# BareDuino_schematic.net
KiCad netlist of a schematic drawn in EAGLE
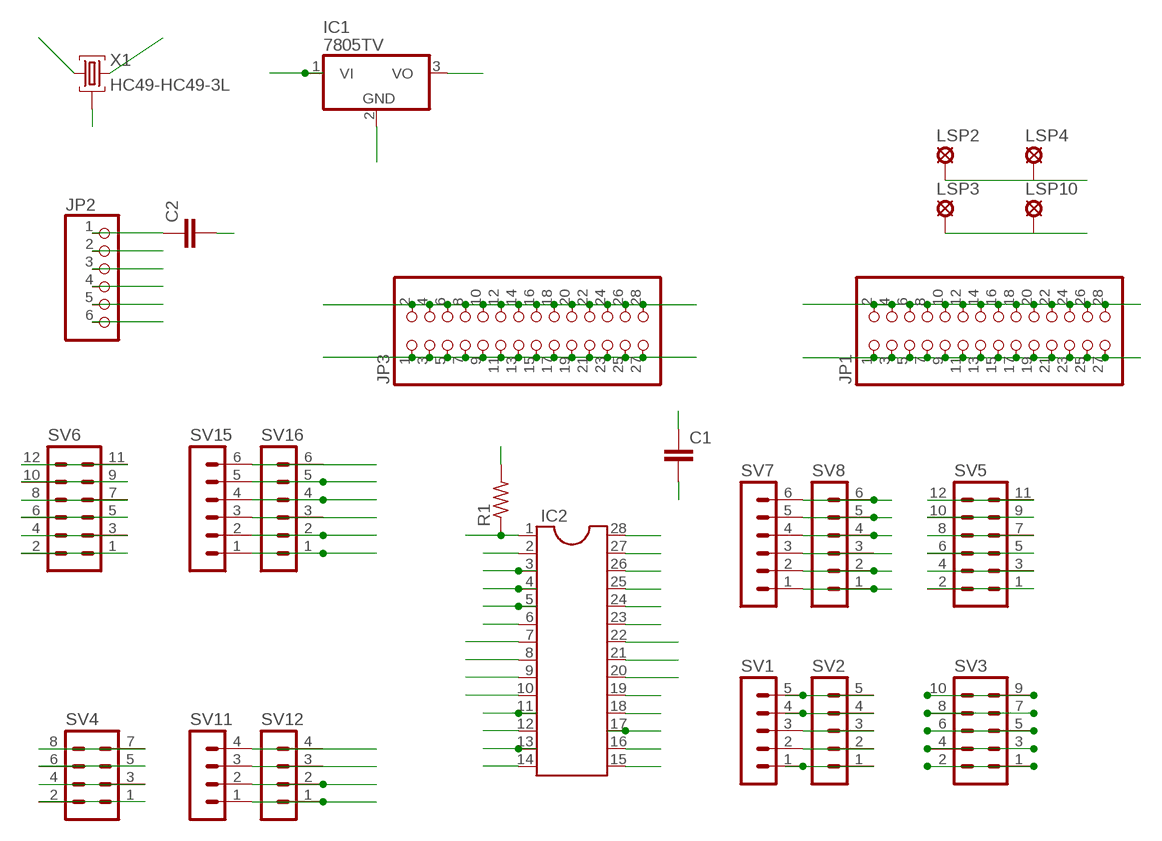
[diagram p0: schematic, sheet 1]

(export (version "E")
  (design (tool "Eeschema 10.0.6"))
  (components
    (comp (ref "C1")
      (value "C5/2.5")
      (footprint "eagle-import:C5B2.5")
      (libsource (lib "eagle-import") (part "C5/2.5"))
    )
    (comp (ref "C2")
      (value "C5/2.5")
      (footprint "eagle-import:C5B2.5")
      (libsource (lib "eagle-import") (part "C5/2.5"))
    )
    (comp (ref "IC1")
      (value "7805TV")
      (footprint "eagle-import:TO220V")
      (libsource (lib "eagle-import") (part "78TV05"))
    )
    (comp (ref "IC2")
      (value "DIL28-3")
      (footprint "eagle-import:DIL28-3")
      (libsource (lib "eagle-import") (part "DIL28-3"))
    )
    (comp (ref "JP1")
      (value "PINHD-2X14")
      (footprint "eagle-import:2X14")
      (libsource (lib "eagle-import") (part "PINHD-2X14"))
    )
    (comp (ref "JP2")
      (value "PINHD-1X6")
      (footprint "eagle-import:1X06")
      (libsource (lib "eagle-import") (part "PINHD-1X6"))
    )
    (comp (ref "JP3")
      (value "PINHD-2X14")
      (footprint "eagle-import:2X14")
      (libsource (lib "eagle-import") (part "PINHD-2X14"))
    )
    (comp (ref "LSP2")
      (value "SE14")
      (footprint "eagle-import:SE14")
      (libsource (lib "eagle-import") (part "SE14"))
    )
    (comp (ref "LSP3")
      (value "SE14")
      (footprint "eagle-import:SE14")
      (libsource (lib "eagle-import") (part "SE14"))
    )
    (comp (ref "LSP4")
      (value "LSP10")
      (footprint "eagle-import:LSP10")
      (libsource (lib "eagle-import") (part "LSP10"))
    )
    (comp (ref "LSP10")
      (value "LSP10")
      (footprint "eagle-import:LSP10")
      (libsource (lib "eagle-import") (part "LSP10"))
    )
    (comp (ref "R1")
      (value "R-US_0204/5")
      (footprint "eagle-import:0204_5")
      (libsource (lib "eagle-import") (part "R-US_0204/5"))
    )
    (comp (ref "SV1")
      (value "MA05-1")
      (footprint "eagle-import:MA05-1")
      (libsource (lib "eagle-import") (part "MA05-1"))
    )
    (comp (ref "SV2")
      (value "MA05-1")
      (footprint "eagle-import:MA05-1")
      (libsource (lib "eagle-import") (part "MA05-1"))
    )
    (comp (ref "SV3")
      (value "MA05-2")
      (footprint "eagle-import:MA05-2")
      (libsource (lib "eagle-import") (part "MA05-2"))
    )
    (comp (ref "SV4")
      (value "MA04-2")
      (footprint "eagle-import:MA04-2")
      (libsource (lib "eagle-import") (part "MA04-2"))
    )
    (comp (ref "SV5")
      (value "MA06-2")
      (footprint "eagle-import:MA06-2")
      (libsource (lib "eagle-import") (part "MA06-2"))
    )
    (comp (ref "SV6")
      (value "MA06-2")
      (footprint "eagle-import:MA06-2")
      (libsource (lib "eagle-import") (part "MA06-2"))
    )
    (comp (ref "SV7")
      (value "MA06-1")
      (footprint "eagle-import:MA06-1")
      (libsource (lib "eagle-import") (part "MA06-1"))
    )
    (comp (ref "SV8")
      (value "MA06-1")
      (footprint "eagle-import:MA06-1")
      (libsource (lib "eagle-import") (part "MA06-1"))
    )
    (comp (ref "SV11")
      (value "MA04-1")
      (footprint "eagle-import:MA04-1")
      (libsource (lib "eagle-import") (part "MA04-1"))
    )
    (comp (ref "SV12")
      (value "MA04-1")
      (footprint "eagle-import:MA04-1")
      (libsource (lib "eagle-import") (part "MA04-1"))
    )
    (comp (ref "SV15")
      (value "MA06-1")
      (footprint "eagle-import:MA06-1")
      (libsource (lib "eagle-import") (part "MA06-1"))
    )
    (comp (ref "SV16")
      (value "MA06-1")
      (footprint "eagle-import:MA06-1")
      (libsource (lib "eagle-import") (part "MA06-1"))
    )
    (comp (ref "X1")
      (value "HC49-HC49-3L")
      (footprint "eagle-import:HC49-3L")
      (libsource (lib "eagle-import") (part "HC49-HC49-3L"))
    )
  )
  (nets
    (net (code "1") (name "/CLK-9") (class "Default")
      (node (ref "IC2") (pin "9") (pinfunction "9_9") (pintype "passive"))
      (node (ref "X1") (pin "1") (pinfunction "1_1") (pintype "passive"))
    )
    (net (code "2") (name "/CLK-10") (class "Default")
      (node (ref "IC2") (pin "10") (pinfunction "10_10") (pintype "passive"))
      (node (ref "X1") (pin "3") (pinfunction "3_3") (pintype "passive"))
    )
    (net (code "3") (name "/DIP2") (class "Default")
      (node (ref "IC2") (pin "2") (pinfunction "2_2") (pintype "passive"))
      (node (ref "JP2") (pin "3") (pinfunction "3_3") (pintype "passive"))
      (node (ref "SV15") (pin "5") (pinfunction "5_5") (pintype "passive"))
      (node (ref "SV16") (pin "5") (pinfunction "5_5") (pintype "passive"))
    )
    (net (code "4") (name "/DIP3") (class "Default")
      (node (ref "IC2") (pin "3") (pinfunction "3_3") (pintype "passive"))
      (node (ref "JP2") (pin "2") (pinfunction "2_2") (pintype "passive"))
      (node (ref "SV15") (pin "4") (pinfunction "4_4") (pintype "passive"))
      (node (ref "SV16") (pin "4") (pinfunction "4_4") (pintype "passive"))
    )
    (net (code "5") (name "/DIP4") (class "Default")
      (node (ref "IC2") (pin "4") (pinfunction "4_4") (pintype "passive"))
      (node (ref "SV15") (pin "3") (pinfunction "3_3") (pintype "passive"))
      (node (ref "SV16") (pin "3") (pinfunction "3_3") (pintype "passive"))
    )
    (net (code "6") (name "/DIP5") (class "Default")
      (node (ref "IC2") (pin "5") (pinfunction "5_5") (pintype "passive"))
      (node (ref "SV15") (pin "2") (pinfunction "2_2") (pintype "passive"))
      (node (ref "SV16") (pin "2") (pinfunction "2_2") (pintype "passive"))
    )
    (net (code "7") (name "/DIP6") (class "Default")
      (node (ref "IC2") (pin "6") (pinfunction "6_6") (pintype "passive"))
      (node (ref "SV15") (pin "1") (pinfunction "1_1") (pintype "passive"))
      (node (ref "SV16") (pin "1") (pinfunction "1_1") (pintype "passive"))
    )
    (net (code "8") (name "/DIP11") (class "Default")
      (node (ref "IC2") (pin "11") (pinfunction "11_11") (pintype "passive"))
      (node (ref "SV11") (pin "4") (pinfunction "4_4") (pintype "passive"))
      (node (ref "SV12") (pin "4") (pinfunction "4_4") (pintype "passive"))
    )
    (net (code "9") (name "/DIP12") (class "Default")
      (node (ref "IC2") (pin "12") (pinfunction "12_12") (pintype "passive"))
      (node (ref "SV11") (pin "3") (pinfunction "3_3") (pintype "passive"))
      (node (ref "SV12") (pin "3") (pinfunction "3_3") (pintype "passive"))
    )
    (net (code "10") (name "/DIP13") (class "Default")
      (node (ref "IC2") (pin "13") (pinfunction "13_13") (pintype "passive"))
      (node (ref "SV11") (pin "2") (pinfunction "2_2") (pintype "passive"))
      (node (ref "SV12") (pin "2") (pinfunction "2_2") (pintype "passive"))
    )
    (net (code "11") (name "/DIP14") (class "Default")
      (node (ref "IC2") (pin "14") (pinfunction "14_14") (pintype "passive"))
      (node (ref "SV11") (pin "1") (pinfunction "1_1") (pintype "passive"))
      (node (ref "SV12") (pin "1") (pinfunction "1_1") (pintype "passive"))
    )
    (net (code "12") (name "/DIP15") (class "Default")
      (node (ref "IC2") (pin "15") (pinfunction "15_15") (pintype "passive"))
      (node (ref "SV1") (pin "1") (pinfunction "1_1") (pintype "passive"))
      (node (ref "SV2") (pin "1") (pinfunction "1_1") (pintype "passive"))
    )
    (net (code "13") (name "/DIP16") (class "Default")
      (node (ref "IC2") (pin "16") (pinfunction "16_16") (pintype "passive"))
      (node (ref "SV1") (pin "2") (pinfunction "2_2") (pintype "passive"))
      (node (ref "SV2") (pin "2") (pinfunction "2_2") (pintype "passive"))
    )
    (net (code "14") (name "/DIP17") (class "Default")
      (node (ref "IC2") (pin "17") (pinfunction "17_17") (pintype "passive"))
      (node (ref "SV1") (pin "3") (pinfunction "3_3") (pintype "passive"))
      (node (ref "SV2") (pin "3") (pinfunction "3_3") (pintype "passive"))
    )
    (net (code "15") (name "/DIP18") (class "Default")
      (node (ref "IC2") (pin "18") (pinfunction "18_18") (pintype "passive"))
      (node (ref "SV1") (pin "4") (pinfunction "4_4") (pintype "passive"))
      (node (ref "SV2") (pin "4") (pinfunction "4_4") (pintype "passive"))
    )
    (net (code "16") (name "/DIP19") (class "Default")
      (node (ref "IC2") (pin "19") (pinfunction "19_19") (pintype "passive"))
      (node (ref "SV1") (pin "5") (pinfunction "5_5") (pintype "passive"))
      (node (ref "SV2") (pin "5") (pinfunction "5_5") (pintype "passive"))
    )
    (net (code "17") (name "/DIP23") (class "Default")
      (node (ref "IC2") (pin "23") (pinfunction "23_23") (pintype "passive"))
      (node (ref "SV7") (pin "1") (pinfunction "1_1") (pintype "passive"))
      (node (ref "SV8") (pin "1") (pinfunction "1_1") (pintype "passive"))
    )
    (net (code "18") (name "/DIP24") (class "Default")
      (node (ref "IC2") (pin "24") (pinfunction "24_24") (pintype "passive"))
      (node (ref "SV7") (pin "2") (pinfunction "2_2") (pintype "passive"))
      (node (ref "SV8") (pin "2") (pinfunction "2_2") (pintype "passive"))
    )
    (net (code "19") (name "/DIP25") (class "Default")
      (node (ref "IC2") (pin "25") (pinfunction "25_25") (pintype "passive"))
      (node (ref "SV7") (pin "3") (pinfunction "3_3") (pintype "passive"))
      (node (ref "SV8") (pin "3") (pinfunction "3_3") (pintype "passive"))
    )
    (net (code "20") (name "/DIP26") (class "Default")
      (node (ref "IC2") (pin "26") (pinfunction "26_26") (pintype "passive"))
      (node (ref "SV7") (pin "4") (pinfunction "4_4") (pintype "passive"))
      (node (ref "SV8") (pin "4") (pinfunction "4_4") (pintype "passive"))
    )
    (net (code "21") (name "/DIP27") (class "Default")
      (node (ref "IC2") (pin "27") (pinfunction "27_27") (pintype "passive"))
      (node (ref "SV7") (pin "5") (pinfunction "5_5") (pintype "passive"))
      (node (ref "SV8") (pin "5") (pinfunction "5_5") (pintype "passive"))
    )
    (net (code "22") (name "/DIP28") (class "Default")
      (node (ref "IC2") (pin "28") (pinfunction "28_28") (pintype "passive"))
      (node (ref "SV7") (pin "6") (pinfunction "6_6") (pintype "passive"))
      (node (ref "SV8") (pin "6") (pinfunction "6_6") (pintype "passive"))
    )
    (net (code "23") (name "/GND") (class "Default")
      (node (ref "C1") (pin "1") (pinfunction "1_1") (pintype "passive"))
      (node (ref "IC1") (pin "2") (pinfunction "GND_2") (pintype "passive"))
      (node (ref "IC2") (pin "22") (pinfunction "22_22") (pintype "passive"))
      (node (ref "IC2") (pin "8") (pinfunction "8_8") (pintype "passive"))
      (node (ref "JP1") (pin "10") (pinfunction "10_10") (pintype "passive"))
      (node (ref "JP1") (pin "12") (pinfunction "12_12") (pintype "passive"))
      (node (ref "JP1") (pin "14") (pinfunction "14_14") (pintype "passive"))
      (node (ref "JP1") (pin "16") (pinfunction "16_16") (pintype "passive"))
      (node (ref "JP1") (pin "18") (pinfunction "18_18") (pintype "passive"))
      (node (ref "JP1") (pin "2") (pinfunction "2_2") (pintype "passive"))
      (node (ref "JP1") (pin "20") (pinfunction "20_20") (pintype "passive"))
      (node (ref "JP1") (pin "22") (pinfunction "22_22") (pintype "passive"))
      (node (ref "JP1") (pin "24") (pinfunction "24_24") (pintype "passive"))
      (node (ref "JP1") (pin "26") (pinfunction "26_26") (pintype "passive"))
      (node (ref "JP1") (pin "28") (pinfunction "28_28") (pintype "passive"))
      (node (ref "JP1") (pin "4") (pinfunction "4_4") (pintype "passive"))
      (node (ref "JP1") (pin "6") (pinfunction "6_6") (pintype "passive"))
      (node (ref "JP1") (pin "8") (pinfunction "8_8") (pintype "passive"))
      (node (ref "JP2") (pin "5") (pinfunction "5_5") (pintype "passive"))
      (node (ref "JP2") (pin "6") (pinfunction "6_6") (pintype "passive"))
      (node (ref "JP3") (pin "1") (pinfunction "1_1") (pintype "passive"))
      (node (ref "JP3") (pin "11") (pinfunction "11_11") (pintype "passive"))
      (node (ref "JP3") (pin "13") (pinfunction "13_13") (pintype "passive"))
      (node (ref "JP3") (pin "15") (pinfunction "15_15") (pintype "passive"))
      (node (ref "JP3") (pin "17") (pinfunction "17_17") (pintype "passive"))
      (node (ref "JP3") (pin "19") (pinfunction "19_19") (pintype "passive"))
      (node (ref "JP3") (pin "21") (pinfunction "21_21") (pintype "passive"))
      (node (ref "JP3") (pin "23") (pinfunction "23_23") (pintype "passive"))
      (node (ref "JP3") (pin "25") (pinfunction "25_25") (pintype "passive"))
      (node (ref "JP3") (pin "27") (pinfunction "27_27") (pintype "passive"))
      (node (ref "JP3") (pin "3") (pinfunction "3_3") (pintype "passive"))
      (node (ref "JP3") (pin "5") (pinfunction "5_5") (pintype "passive"))
      (node (ref "JP3") (pin "7") (pinfunction "7_7") (pintype "passive"))
      (node (ref "JP3") (pin "9") (pinfunction "9_9") (pintype "passive"))
      (node (ref "LSP10") (pin "MP") (pinfunction "MP_MP") (pintype "passive"))
      (node (ref "LSP3") (pin "MP") (pinfunction "MP_MP") (pintype "passive"))
      (node (ref "X1") (pin "2") (pinfunction "2_2") (pintype "passive"))
    )
    (net (code "24") (name "/RST") (class "Default")
      (node (ref "C2") (pin "2") (pinfunction "2_2") (pintype "passive"))
      (node (ref "IC2") (pin "1") (pinfunction "1_1") (pintype "passive"))
      (node (ref "R1") (pin "1") (pinfunction "1_1") (pintype "passive"))
      (node (ref "SV15") (pin "6") (pinfunction "6_6") (pintype "passive"))
      (node (ref "SV16") (pin "6") (pinfunction "6_6") (pintype "passive"))
    )
    (net (code "25") (name "/VCC") (class "Default")
      (node (ref "C1") (pin "2") (pinfunction "2_2") (pintype "passive"))
      (node (ref "IC1") (pin "3") (pinfunction "VO_3") (pintype "passive"))
      (node (ref "IC2") (pin "20") (pinfunction "20_20") (pintype "passive"))
      (node (ref "IC2") (pin "21") (pinfunction "21_21") (pintype "passive"))
      (node (ref "IC2") (pin "7") (pinfunction "7_7") (pintype "passive"))
      (node (ref "JP1") (pin "1") (pinfunction "1_1") (pintype "passive"))
      (node (ref "JP1") (pin "11") (pinfunction "11_11") (pintype "passive"))
      (node (ref "JP1") (pin "13") (pinfunction "13_13") (pintype "passive"))
      (node (ref "JP1") (pin "15") (pinfunction "15_15") (pintype "passive"))
      (node (ref "JP1") (pin "17") (pinfunction "17_17") (pintype "passive"))
      (node (ref "JP1") (pin "19") (pinfunction "19_19") (pintype "passive"))
      (node (ref "JP1") (pin "21") (pinfunction "21_21") (pintype "passive"))
      (node (ref "JP1") (pin "23") (pinfunction "23_23") (pintype "passive"))
      (node (ref "JP1") (pin "25") (pinfunction "25_25") (pintype "passive"))
      (node (ref "JP1") (pin "27") (pinfunction "27_27") (pintype "passive"))
      (node (ref "JP1") (pin "3") (pinfunction "3_3") (pintype "passive"))
      (node (ref "JP1") (pin "5") (pinfunction "5_5") (pintype "passive"))
      (node (ref "JP1") (pin "7") (pinfunction "7_7") (pintype "passive"))
      (node (ref "JP1") (pin "9") (pinfunction "9_9") (pintype "passive"))
      (node (ref "JP2") (pin "4") (pinfunction "4_4") (pintype "passive"))
      (node (ref "JP3") (pin "10") (pinfunction "10_10") (pintype "passive"))
      (node (ref "JP3") (pin "12") (pinfunction "12_12") (pintype "passive"))
      (node (ref "JP3") (pin "14") (pinfunction "14_14") (pintype "passive"))
      (node (ref "JP3") (pin "16") (pinfunction "16_16") (pintype "passive"))
      (node (ref "JP3") (pin "18") (pinfunction "18_18") (pintype "passive"))
      (node (ref "JP3") (pin "2") (pinfunction "2_2") (pintype "passive"))
      (node (ref "JP3") (pin "20") (pinfunction "20_20") (pintype "passive"))
      (node (ref "JP3") (pin "22") (pinfunction "22_22") (pintype "passive"))
      (node (ref "JP3") (pin "24") (pinfunction "24_24") (pintype "passive"))
      (node (ref "JP3") (pin "26") (pinfunction "26_26") (pintype "passive"))
      (node (ref "JP3") (pin "28") (pinfunction "28_28") (pintype "passive"))
      (node (ref "JP3") (pin "4") (pinfunction "4_4") (pintype "passive"))
      (node (ref "JP3") (pin "6") (pinfunction "6_6") (pintype "passive"))
      (node (ref "JP3") (pin "8") (pinfunction "8_8") (pintype "passive"))
      (node (ref "R1") (pin "2") (pinfunction "2_2") (pintype "passive"))
    )
    (net (code "26") (name "/VIN") (class "Default")
      (node (ref "IC1") (pin "1") (pinfunction "VI_1") (pintype "input"))
      (node (ref "LSP2") (pin "MP") (pinfunction "MP_MP") (pintype "passive"))
      (node (ref "LSP4") (pin "MP") (pinfunction "MP_MP") (pintype "passive"))
    )
    (net (code "27") (name "Net-(C2-Pad1)") (class "Default")
      (node (ref "C2") (pin "1") (pinfunction "1_1") (pintype "passive"))
      (node (ref "JP2") (pin "1") (pinfunction "1_1") (pintype "passive"))
    )
    (net (code "28") (name "Net-(SV3-Pad1)") (class "Default")
      (node (ref "SV3") (pin "1") (pinfunction "1_1") (pintype "passive"))
      (node (ref "SV3") (pin "2") (pinfunction "2_2") (pintype "passive"))
    )
    (net (code "29") (name "Net-(SV3-Pad3)") (class "Default")
      (node (ref "SV3") (pin "3") (pinfunction "3_3") (pintype "passive"))
      (node (ref "SV3") (pin "4") (pinfunction "4_4") (pintype "passive"))
    )
    (net (code "30") (name "Net-(SV3-Pad5)") (class "Default")
      (node (ref "SV3") (pin "5") (pinfunction "5_5") (pintype "passive"))
      (node (ref "SV3") (pin "6") (pinfunction "6_6") (pintype "passive"))
    )
    (net (code "31") (name "Net-(SV3-Pad7)") (class "Default")
      (node (ref "SV3") (pin "7") (pinfunction "7_7") (pintype "passive"))
      (node (ref "SV3") (pin "8") (pinfunction "8_8") (pintype "passive"))
    )
    (net (code "32") (name "Net-(SV3-Pad10)") (class "Default")
      (node (ref "SV3") (pin "10") (pinfunction "10_10") (pintype "passive"))
      (node (ref "SV3") (pin "9") (pinfunction "9_9") (pintype "passive"))
    )
    (net (code "33") (name "Net-(SV4-Pad1)") (class "Default")
      (node (ref "SV4") (pin "1") (pinfunction "1_1") (pintype "passive"))
      (node (ref "SV4") (pin "2") (pinfunction "2_2") (pintype "passive"))
    )
    (net (code "34") (name "Net-(SV4-Pad3)") (class "Default")
      (node (ref "SV4") (pin "3") (pinfunction "3_3") (pintype "passive"))
      (node (ref "SV4") (pin "4") (pinfunction "4_4") (pintype "passive"))
    )
    (net (code "35") (name "Net-(SV4-Pad5)") (class "Default")
      (node (ref "SV4") (pin "5") (pinfunction "5_5") (pintype "passive"))
      (node (ref "SV4") (pin "6") (pinfunction "6_6") (pintype "passive"))
    )
    (net (code "36") (name "Net-(SV4-Pad7)") (class "Default")
      (node (ref "SV4") (pin "7") (pinfunction "7_7") (pintype "passive"))
      (node (ref "SV4") (pin "8") (pinfunction "8_8") (pintype "passive"))
    )
    (net (code "37") (name "Net-(SV5-Pad1)") (class "Default")
      (node (ref "SV5") (pin "1") (pinfunction "1_1") (pintype "passive"))
      (node (ref "SV5") (pin "2") (pinfunction "2_2") (pintype "passive"))
    )
    (net (code "38") (name "Net-(SV5-Pad3)") (class "Default")
      (node (ref "SV5") (pin "3") (pinfunction "3_3") (pintype "passive"))
      (node (ref "SV5") (pin "4") (pinfunction "4_4") (pintype "passive"))
    )
    (net (code "39") (name "Net-(SV5-Pad5)") (class "Default")
      (node (ref "SV5") (pin "5") (pinfunction "5_5") (pintype "passive"))
      (node (ref "SV5") (pin "6") (pinfunction "6_6") (pintype "passive"))
    )
    (net (code "40") (name "Net-(SV5-Pad7)") (class "Default")
      (node (ref "SV5") (pin "7") (pinfunction "7_7") (pintype "passive"))
      (node (ref "SV5") (pin "8") (pinfunction "8_8") (pintype "passive"))
    )
    (net (code "41") (name "Net-(SV5-Pad10)") (class "Default")
      (node (ref "SV5") (pin "10") (pinfunction "10_10") (pintype "passive"))
      (node (ref "SV5") (pin "9") (pinfunction "9_9") (pintype "passive"))
    )
    (net (code "42") (name "Net-(SV5-Pad11)") (class "Default")
      (node (ref "SV5") (pin "11") (pinfunction "11_11") (pintype "passive"))
      (node (ref "SV5") (pin "12") (pinfunction "12_12") (pintype "passive"))
    )
    (net (code "43") (name "Net-(SV6-Pad1)") (class "Default")
      (node (ref "SV6") (pin "1") (pinfunction "1_1") (pintype "passive"))
      (node (ref "SV6") (pin "2") (pinfunction "2_2") (pintype "passive"))
    )
    (net (code "44") (name "Net-(SV6-Pad3)") (class "Default")
      (node (ref "SV6") (pin "3") (pinfunction "3_3") (pintype "passive"))
      (node (ref "SV6") (pin "4") (pinfunction "4_4") (pintype "passive"))
    )
    (net (code "45") (name "Net-(SV6-Pad5)") (class "Default")
      (node (ref "SV6") (pin "5") (pinfunction "5_5") (pintype "passive"))
      (node (ref "SV6") (pin "6") (pinfunction "6_6") (pintype "passive"))
    )
    (net (code "46") (name "Net-(SV6-Pad7)") (class "Default")
      (node (ref "SV6") (pin "7") (pinfunction "7_7") (pintype "passive"))
      (node (ref "SV6") (pin "8") (pinfunction "8_8") (pintype "passive"))
    )
    (net (code "47") (name "Net-(SV6-Pad10)") (class "Default")
      (node (ref "SV6") (pin "10") (pinfunction "10_10") (pintype "passive"))
      (node (ref "SV6") (pin "9") (pinfunction "9_9") (pintype "passive"))
    )
    (net (code "48") (name "Net-(SV6-Pad11)") (class "Default")
      (node (ref "SV6") (pin "11") (pinfunction "11_11") (pintype "passive"))
      (node (ref "SV6") (pin "12") (pinfunction "12_12") (pintype "passive"))
    )
  )
)
